# Antler.net
KiCad netlist of a schematic drawn in EAGLE
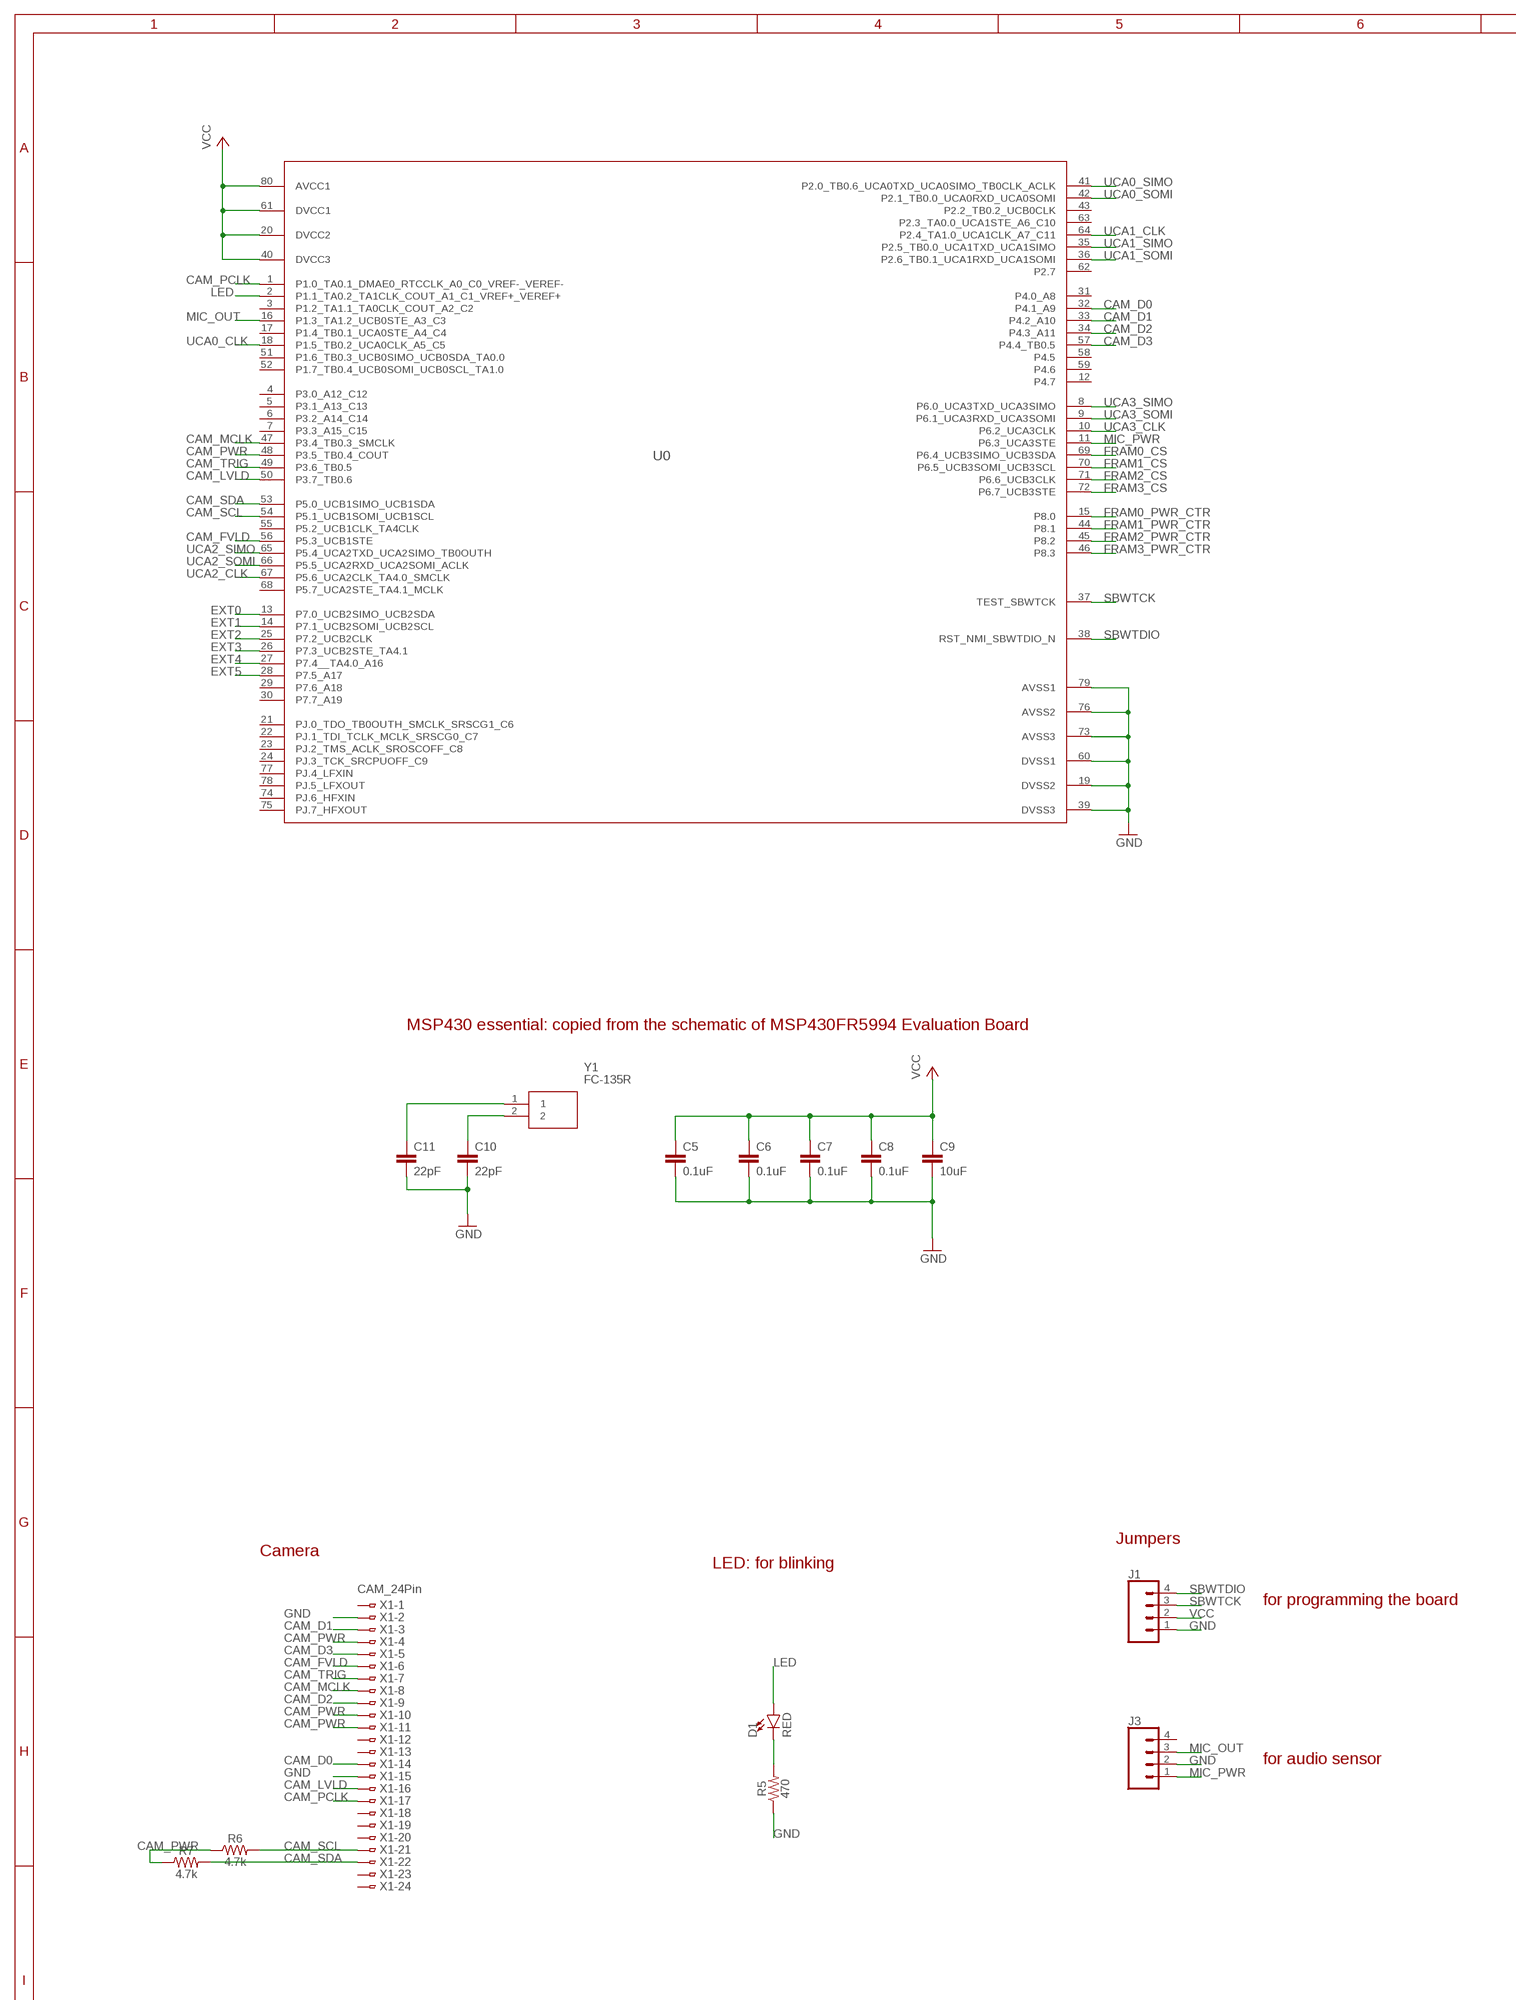
[diagram p0: schematic, sheet 1, part 1 of 2]
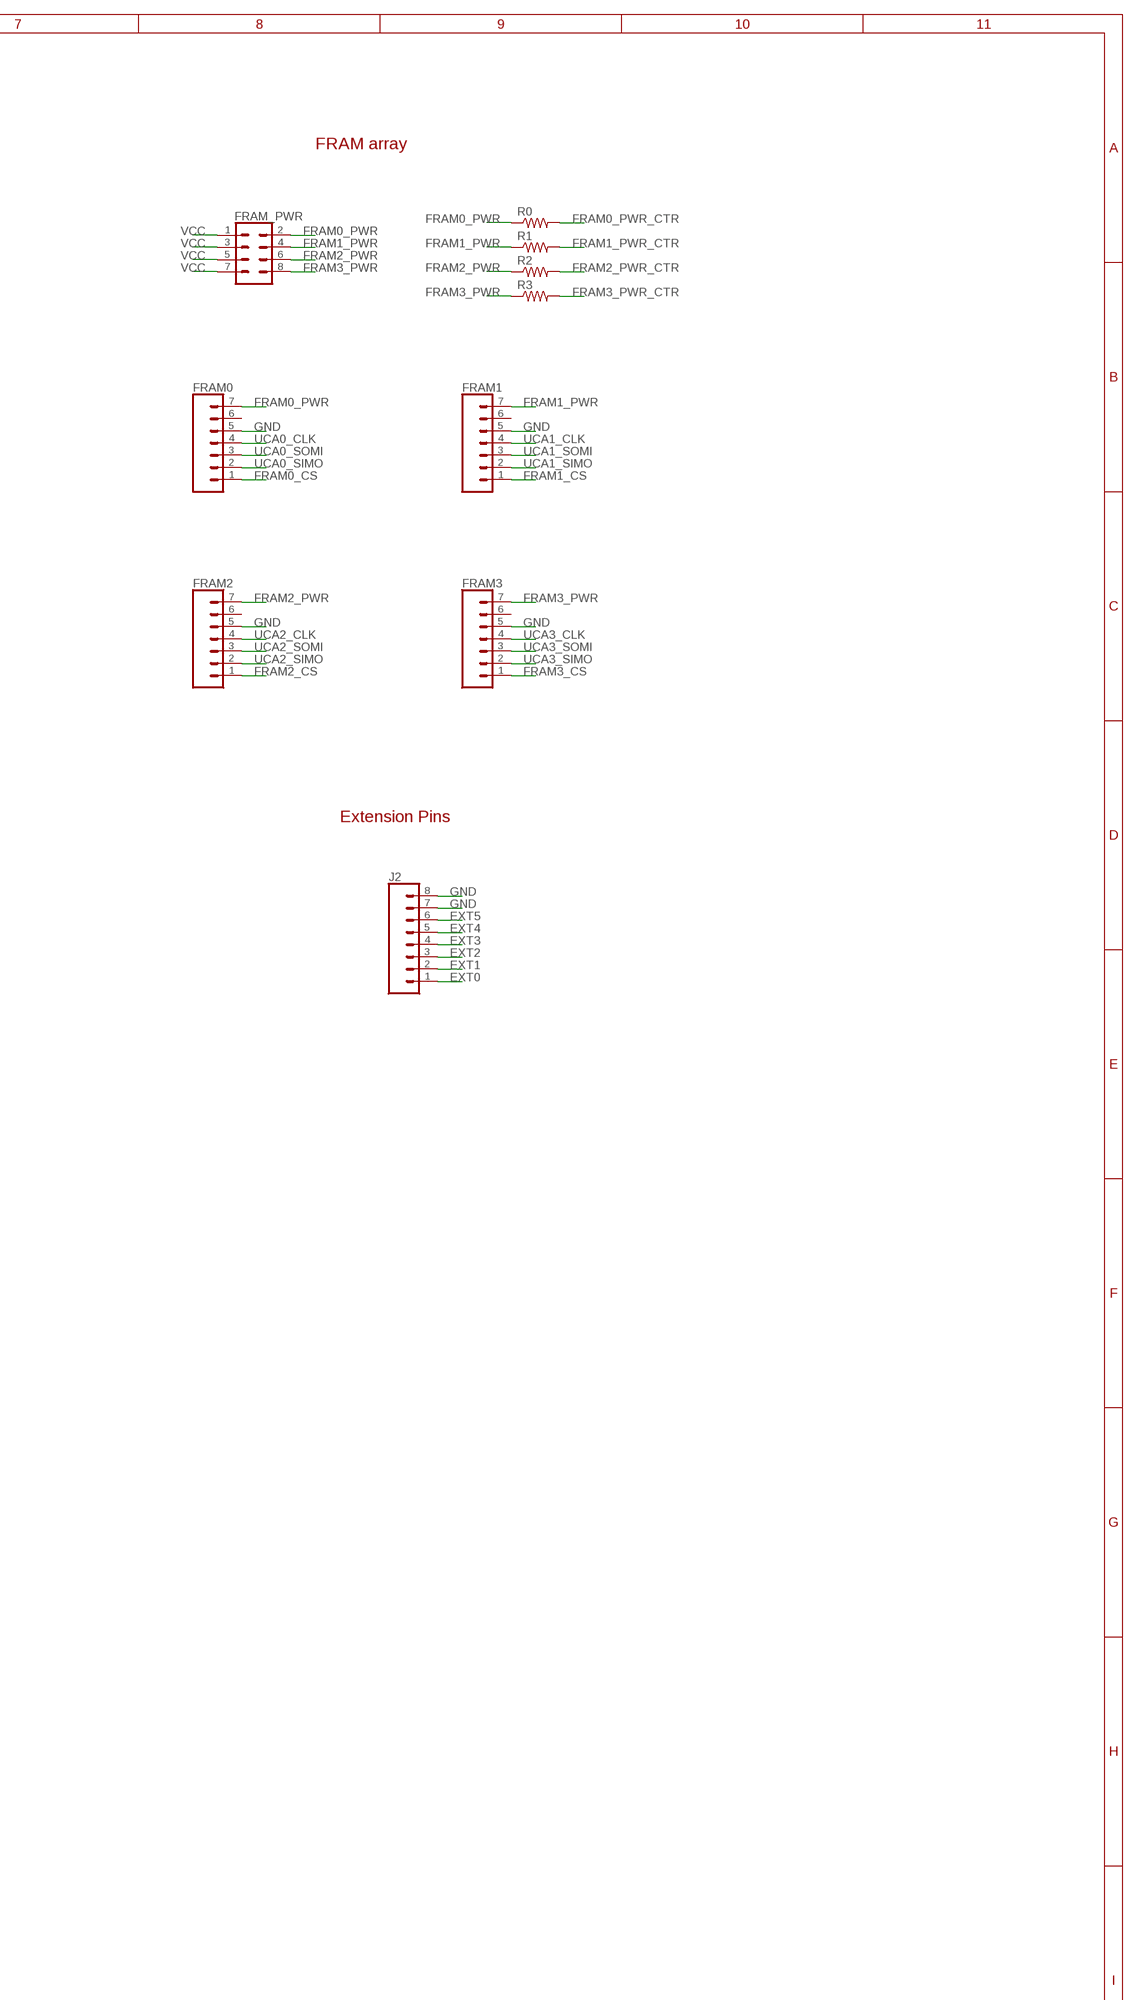
[diagram p1: schematic, sheet 1, part 2 of 2]

(export (version "E")
  (design (tool "Eeschema 10.0.6"))
  (components
    (comp (ref "C5")
      (value "0.1uF")
      (footprint "eagle-import:0603")
      (libsource (lib "eagle-import") (part "0.1UF-0603-25V-5%"))
    )
    (comp (ref "C6")
      (value "0.1uF")
      (footprint "eagle-import:0603")
      (libsource (lib "eagle-import") (part "0.1UF-0603-25V-5%"))
    )
    (comp (ref "C7")
      (value "0.1uF")
      (footprint "eagle-import:0603")
      (libsource (lib "eagle-import") (part "0.1UF-0603-25V-5%"))
    )
    (comp (ref "C8")
      (value "0.1uF")
      (footprint "eagle-import:0603")
      (libsource (lib "eagle-import") (part "0.1UF-0603-25V-5%"))
    )
    (comp (ref "C9")
      (value "10uF")
      (footprint "eagle-import:0603")
      (libsource (lib "eagle-import") (part "10UF-0603-6.3V-20%"))
    )
    (comp (ref "C10")
      (value "22pF")
      (footprint "eagle-import:0603")
      (libsource (lib "eagle-import") (part "22PF-0603-50V-5%"))
    )
    (comp (ref "C11")
      (value "22pF")
      (footprint "eagle-import:0603")
      (libsource (lib "eagle-import") (part "22PF-0603-50V-5%"))
    )
    (comp (ref "D1")
      (value "RED")
      (footprint "eagle-import:LED-0603")
      (libsource (lib "eagle-import") (part "LED-RED0603"))
    )
    (comp (ref "FRAM0")
      (value "CONN_07LOCK")
      (footprint "eagle-import:1X07_LOCK")
      (libsource (lib "eagle-import") (part "CONN_07LOCK"))
    )
    (comp (ref "FRAM1")
      (value "CONN_07LOCK")
      (footprint "eagle-import:1X07_LOCK")
      (libsource (lib "eagle-import") (part "CONN_07LOCK"))
    )
    (comp (ref "FRAM2")
      (value "CONN_07LOCK")
      (footprint "eagle-import:1X07_LOCK")
      (libsource (lib "eagle-import") (part "CONN_07LOCK"))
    )
    (comp (ref "FRAM3")
      (value "CONN_07LOCK")
      (footprint "eagle-import:1X07_LOCK")
      (libsource (lib "eagle-import") (part "CONN_07LOCK"))
    )
    (comp (ref "FRAM_PWR")
      (value "CONN_04X2")
      (footprint "eagle-import:2X4")
      (libsource (lib "eagle-import") (part "CONN_04X2"))
    )
    (comp (ref "J1")
      (value "CONN_04LOCK")
      (footprint "eagle-import:1X04_LOCK")
      (libsource (lib "eagle-import") (part "CONN_04LOCK"))
    )
    (comp (ref "J2")
      (value "CONN_08LOCK")
      (footprint "eagle-import:1X08_LOCK")
      (libsource (lib "eagle-import") (part "CONN_08LOCK"))
    )
    (comp (ref "J3")
      (value "CONN_04LOCK")
      (footprint "eagle-import:1X04_LOCK")
      (libsource (lib "eagle-import") (part "CONN_04LOCK"))
    )
    (comp (ref "R0")
      (value "R-US_R0603")
      (footprint "eagle-import:R0603")
      (libsource (lib "eagle-import") (part "R-US_R0603"))
    )
    (comp (ref "R1")
      (value "R-US_R0603")
      (footprint "eagle-import:R0603")
      (libsource (lib "eagle-import") (part "R-US_R0603"))
    )
    (comp (ref "R2")
      (value "R-US_R0603")
      (footprint "eagle-import:R0603")
      (libsource (lib "eagle-import") (part "R-US_R0603"))
    )
    (comp (ref "R3")
      (value "R-US_R0603")
      (footprint "eagle-import:R0603")
      (libsource (lib "eagle-import") (part "R-US_R0603"))
    )
    (comp (ref "R5")
      (value "470")
      (footprint "eagle-import:0603")
      (libsource (lib "eagle-import") (part "470OHM-0603-1/10W-1%"))
    )
    (comp (ref "R6")
      (value "4.7k")
      (footprint "eagle-import:0603")
      (libsource (lib "eagle-import") (part "4.7KOHM-0603-1/10W-1%"))
    )
    (comp (ref "R7")
      (value "4.7k")
      (footprint "eagle-import:0603")
      (libsource (lib "eagle-import") (part "4.7KOHM-0603-1/10W-1%"))
    )
    (comp (ref "U0")
      (value "MSP430FR5994PN")
      (footprint "eagle-import:PN0080A_N")
      (fields
        (field (name "MANUFACTURER") "Texas Instruments")
        (field (name "PARTNUMBER") "MSP430FR5994IPNR")
      )
      (libsource (lib "eagle-import") (part "MSP430FR5994IPN"))
    )
    (comp (ref "X1")
      (value "CAM_24Pin")
      (footprint "eagle-import:FH12-24S-0.5SH")
      (fields (field (name "MPN") "FH12-24S-0.5SH(55)"))
      (libsource (lib "eagle-import") (part "FH12-24S-0.5SH"))
    )
    (comp (ref "Y1")
      (value "FC-135R")
      (footprint "eagle-import:FC135327680KAAG0")
      (libsource (lib "eagle-import") (part "FC-135R"))
    )
  )
  (nets
    (net (code "1") (name "/CAM_D0") (class "Default")
      (node (ref "U0") (pin "32") (pinfunction "P4.1_A9_32") (pintype "bidirectional"))
      (node (ref "X1") (pin "14") (pinfunction "1_14") (pintype "passive"))
    )
    (net (code "2") (name "/CAM_D1") (class "Default")
      (node (ref "U0") (pin "33") (pinfunction "P4.2_A10_33") (pintype "bidirectional"))
      (node (ref "X1") (pin "3") (pinfunction "1_3") (pintype "passive"))
    )
    (net (code "3") (name "/CAM_D2") (class "Default")
      (node (ref "U0") (pin "34") (pinfunction "P4.3_A11_34") (pintype "bidirectional"))
      (node (ref "X1") (pin "9") (pinfunction "1_9") (pintype "passive"))
    )
    (net (code "4") (name "/CAM_D3") (class "Default")
      (node (ref "U0") (pin "57") (pinfunction "P4.4_TB0.5_57") (pintype "bidirectional"))
      (node (ref "X1") (pin "5") (pinfunction "1_5") (pintype "passive"))
    )
    (net (code "5") (name "/CAM_FVLD") (class "Default")
      (node (ref "U0") (pin "56") (pinfunction "P5.3_UCB1STE_56") (pintype "bidirectional"))
      (node (ref "X1") (pin "6") (pinfunction "1_6") (pintype "passive"))
    )
    (net (code "6") (name "/CAM_LVLD") (class "Default")
      (node (ref "U0") (pin "50") (pinfunction "P3.7_TB0.6_50") (pintype "bidirectional"))
      (node (ref "X1") (pin "16") (pinfunction "1_16") (pintype "passive"))
    )
    (net (code "7") (name "/CAM_MCLK") (class "Default")
      (node (ref "U0") (pin "47") (pinfunction "P3.4_TB0.3_SMCLK_47") (pintype "bidirectional"))
      (node (ref "X1") (pin "8") (pinfunction "1_8") (pintype "passive"))
    )
    (net (code "8") (name "/CAM_PCLK") (class "Default")
      (node (ref "U0") (pin "1") (pinfunction "P1.0_TA0.1_DMAE0_RTCCLK_A0_C0_VREF-_VEREF-_1") (pintype "bidirectional"))
      (node (ref "X1") (pin "17") (pinfunction "1_17") (pintype "passive"))
    )
    (net (code "9") (name "/CAM_PWR") (class "Default")
      (node (ref "R6") (pin "1") (pinfunction "1_1") (pintype "passive"))
      (node (ref "R7") (pin "1") (pinfunction "1_1") (pintype "passive"))
      (node (ref "U0") (pin "48") (pinfunction "P3.5_TB0.4_COUT_48") (pintype "bidirectional"))
      (node (ref "X1") (pin "10") (pinfunction "1_10") (pintype "passive"))
      (node (ref "X1") (pin "11") (pinfunction "1_11") (pintype "passive"))
      (node (ref "X1") (pin "4") (pinfunction "1_4") (pintype "passive"))
    )
    (net (code "10") (name "/CAM_SCL") (class "Default")
      (node (ref "R6") (pin "2") (pinfunction "2_2") (pintype "passive"))
      (node (ref "U0") (pin "54") (pinfunction "P5.1_UCB1SOMI_UCB1SCL_54") (pintype "bidirectional"))
      (node (ref "X1") (pin "21") (pinfunction "1_21") (pintype "passive"))
    )
    (net (code "11") (name "/CAM_SDA") (class "Default")
      (node (ref "R7") (pin "2") (pinfunction "2_2") (pintype "passive"))
      (node (ref "U0") (pin "53") (pinfunction "P5.0_UCB1SIMO_UCB1SDA_53") (pintype "bidirectional"))
      (node (ref "X1") (pin "22") (pinfunction "1_22") (pintype "passive"))
    )
    (net (code "12") (name "/CAM_TRIG") (class "Default")
      (node (ref "U0") (pin "49") (pinfunction "P3.6_TB0.5_49") (pintype "bidirectional"))
      (node (ref "X1") (pin "7") (pinfunction "1_7") (pintype "passive"))
    )
    (net (code "13") (name "/EXT0") (class "Default")
      (node (ref "J2") (pin "1") (pinfunction "1_1") (pintype "passive"))
      (node (ref "U0") (pin "13") (pinfunction "P7.0_UCB2SIMO_UCB2SDA_13") (pintype "bidirectional"))
    )
    (net (code "14") (name "/EXT1") (class "Default")
      (node (ref "J2") (pin "2") (pinfunction "2_2") (pintype "passive"))
      (node (ref "U0") (pin "14") (pinfunction "P7.1_UCB2SOMI_UCB2SCL_14") (pintype "bidirectional"))
    )
    (net (code "15") (name "/EXT2") (class "Default")
      (node (ref "J2") (pin "3") (pinfunction "3_3") (pintype "passive"))
      (node (ref "U0") (pin "25") (pinfunction "P7.2_UCB2CLK_25") (pintype "bidirectional"))
    )
    (net (code "16") (name "/EXT3") (class "Default")
      (node (ref "J2") (pin "4") (pinfunction "4_4") (pintype "passive"))
      (node (ref "U0") (pin "26") (pinfunction "P7.3_UCB2STE_TA4.1_26") (pintype "bidirectional"))
    )
    (net (code "17") (name "/EXT4") (class "Default")
      (node (ref "J2") (pin "5") (pinfunction "5_5") (pintype "passive"))
      (node (ref "U0") (pin "27") (pinfunction "P7.4__TA4.0_A16_27") (pintype "bidirectional"))
    )
    (net (code "18") (name "/EXT5") (class "Default")
      (node (ref "J2") (pin "6") (pinfunction "6_6") (pintype "passive"))
      (node (ref "U0") (pin "28") (pinfunction "P7.5_A17_28") (pintype "bidirectional"))
    )
    (net (code "19") (name "/FRAM0_CS") (class "Default")
      (node (ref "FRAM0") (pin "1") (pinfunction "1_1") (pintype "passive"))
      (node (ref "U0") (pin "69") (pinfunction "P6.4_UCB3SIMO_UCB3SDA_69") (pintype "bidirectional"))
    )
    (net (code "20") (name "/FRAM0_PWR") (class "Default")
      (node (ref "FRAM0") (pin "7") (pinfunction "7_7") (pintype "passive"))
      (node (ref "FRAM_PWR") (pin "2") (pinfunction "2_2") (pintype "passive"))
      (node (ref "R0") (pin "1") (pinfunction "1_1") (pintype "passive"))
    )
    (net (code "21") (name "/FRAM0_PWR_CTR") (class "Default")
      (node (ref "R0") (pin "2") (pinfunction "2_2") (pintype "passive"))
      (node (ref "U0") (pin "15") (pinfunction "P8.0_15") (pintype "bidirectional"))
    )
    (net (code "22") (name "/FRAM1_CS") (class "Default")
      (node (ref "FRAM1") (pin "1") (pinfunction "1_1") (pintype "passive"))
      (node (ref "U0") (pin "70") (pinfunction "P6.5_UCB3SOMI_UCB3SCL_70") (pintype "bidirectional"))
    )
    (net (code "23") (name "/FRAM1_PWR") (class "Default")
      (node (ref "FRAM1") (pin "7") (pinfunction "7_7") (pintype "passive"))
      (node (ref "FRAM_PWR") (pin "4") (pinfunction "4_4") (pintype "passive"))
      (node (ref "R1") (pin "1") (pinfunction "1_1") (pintype "passive"))
    )
    (net (code "24") (name "/FRAM1_PWR_CTR") (class "Default")
      (node (ref "R1") (pin "2") (pinfunction "2_2") (pintype "passive"))
      (node (ref "U0") (pin "44") (pinfunction "P8.1_44") (pintype "bidirectional"))
    )
    (net (code "25") (name "/FRAM2_CS") (class "Default")
      (node (ref "FRAM2") (pin "1") (pinfunction "1_1") (pintype "passive"))
      (node (ref "U0") (pin "71") (pinfunction "P6.6_UCB3CLK_71") (pintype "bidirectional"))
    )
    (net (code "26") (name "/FRAM2_PWR") (class "Default")
      (node (ref "FRAM2") (pin "7") (pinfunction "7_7") (pintype "passive"))
      (node (ref "FRAM_PWR") (pin "6") (pinfunction "6_6") (pintype "passive"))
      (node (ref "R2") (pin "1") (pinfunction "1_1") (pintype "passive"))
    )
    (net (code "27") (name "/FRAM2_PWR_CTR") (class "Default")
      (node (ref "R2") (pin "2") (pinfunction "2_2") (pintype "passive"))
      (node (ref "U0") (pin "45") (pinfunction "P8.2_45") (pintype "bidirectional"))
    )
    (net (code "28") (name "/FRAM3_CS") (class "Default")
      (node (ref "FRAM3") (pin "1") (pinfunction "1_1") (pintype "passive"))
      (node (ref "U0") (pin "72") (pinfunction "P6.7_UCB3STE_72") (pintype "bidirectional"))
    )
    (net (code "29") (name "/FRAM3_PWR") (class "Default")
      (node (ref "FRAM3") (pin "7") (pinfunction "7_7") (pintype "passive"))
      (node (ref "FRAM_PWR") (pin "8") (pinfunction "8_8") (pintype "passive"))
      (node (ref "R3") (pin "1") (pinfunction "1_1") (pintype "passive"))
    )
    (net (code "30") (name "/FRAM3_PWR_CTR") (class "Default")
      (node (ref "R3") (pin "2") (pinfunction "2_2") (pintype "passive"))
      (node (ref "U0") (pin "46") (pinfunction "P8.3_46") (pintype "bidirectional"))
    )
    (net (code "31") (name "/LED") (class "Default")
      (node (ref "D1") (pin "A") (pinfunction "A_A") (pintype "passive"))
      (node (ref "U0") (pin "2") (pinfunction "P1.1_TA0.2_TA1CLK_COUT_A1_C1_VREF+_VEREF+_2") (pintype "bidirectional"))
    )
    (net (code "32") (name "/MIC_OUT") (class "Default")
      (node (ref "J3") (pin "3") (pinfunction "3_3") (pintype "passive"))
      (node (ref "U0") (pin "16") (pinfunction "P1.3_TA1.2_UCB0STE_A3_C3_16") (pintype "bidirectional"))
    )
    (net (code "33") (name "/MIC_PWR") (class "Default")
      (node (ref "J3") (pin "1") (pinfunction "1_1") (pintype "passive"))
      (node (ref "U0") (pin "11") (pinfunction "P6.3_UCA3STE_11") (pintype "bidirectional"))
    )
    (net (code "34") (name "/SBWTCK") (class "Default")
      (node (ref "J1") (pin "3") (pinfunction "3_3") (pintype "passive"))
      (node (ref "U0") (pin "37") (pinfunction "TEST_SBWTCK_37") (pintype "input"))
    )
    (net (code "35") (name "/SBWTDIO") (class "Default")
      (node (ref "J1") (pin "4") (pinfunction "4_4") (pintype "passive"))
      (node (ref "U0") (pin "38") (pinfunction "RST_NMI_SBWTDIO_N_38") (pintype "bidirectional"))
    )
    (net (code "36") (name "/UCA0_CLK") (class "Default")
      (node (ref "FRAM0") (pin "4") (pinfunction "4_4") (pintype "passive"))
      (node (ref "U0") (pin "18") (pinfunction "P1.5_TB0.2_UCA0CLK_A5_C5_18") (pintype "bidirectional"))
    )
    (net (code "37") (name "/UCA0_SIMO") (class "Default")
      (node (ref "FRAM0") (pin "2") (pinfunction "2_2") (pintype "passive"))
      (node (ref "U0") (pin "41") (pinfunction "P2.0_TB0.6_UCA0TXD_UCA0SIMO_TB0CLK_ACLK_41") (pintype "bidirectional"))
    )
    (net (code "38") (name "/UCA0_SOMI") (class "Default")
      (node (ref "FRAM0") (pin "3") (pinfunction "3_3") (pintype "passive"))
      (node (ref "U0") (pin "42") (pinfunction "P2.1_TB0.0_UCA0RXD_UCA0SOMI_42") (pintype "bidirectional"))
    )
    (net (code "39") (name "/UCA1_CLK") (class "Default")
      (node (ref "FRAM1") (pin "4") (pinfunction "4_4") (pintype "passive"))
      (node (ref "U0") (pin "64") (pinfunction "P2.4_TA1.0_UCA1CLK_A7_C11_64") (pintype "bidirectional"))
    )
    (net (code "40") (name "/UCA1_SIMO") (class "Default")
      (node (ref "FRAM1") (pin "2") (pinfunction "2_2") (pintype "passive"))
      (node (ref "U0") (pin "35") (pinfunction "P2.5_TB0.0_UCA1TXD_UCA1SIMO_35") (pintype "bidirectional"))
    )
    (net (code "41") (name "/UCA1_SOMI") (class "Default")
      (node (ref "FRAM1") (pin "3") (pinfunction "3_3") (pintype "passive"))
      (node (ref "U0") (pin "36") (pinfunction "P2.6_TB0.1_UCA1RXD_UCA1SOMI_36") (pintype "bidirectional"))
    )
    (net (code "42") (name "/UCA2_CLK") (class "Default")
      (node (ref "FRAM2") (pin "4") (pinfunction "4_4") (pintype "passive"))
      (node (ref "U0") (pin "67") (pinfunction "P5.6_UCA2CLK_TA4.0_SMCLK_67") (pintype "bidirectional"))
    )
    (net (code "43") (name "/UCA2_SIMO") (class "Default")
      (node (ref "FRAM2") (pin "2") (pinfunction "2_2") (pintype "passive"))
      (node (ref "U0") (pin "65") (pinfunction "P5.4_UCA2TXD_UCA2SIMO_TB0OUTH_65") (pintype "bidirectional"))
    )
    (net (code "44") (name "/UCA2_SOMI") (class "Default")
      (node (ref "FRAM2") (pin "3") (pinfunction "3_3") (pintype "passive"))
      (node (ref "U0") (pin "66") (pinfunction "P5.5_UCA2RXD_UCA2SOMI_ACLK_66") (pintype "bidirectional"))
    )
    (net (code "45") (name "/UCA3_CLK") (class "Default")
      (node (ref "FRAM3") (pin "4") (pinfunction "4_4") (pintype "passive"))
      (node (ref "U0") (pin "10") (pinfunction "P6.2_UCA3CLK_10") (pintype "bidirectional"))
    )
    (net (code "46") (name "/UCA3_SIMO") (class "Default")
      (node (ref "FRAM3") (pin "2") (pinfunction "2_2") (pintype "passive"))
      (node (ref "U0") (pin "8") (pinfunction "P6.0_UCA3TXD_UCA3SIMO_8") (pintype "bidirectional"))
    )
    (net (code "47") (name "/UCA3_SOMI") (class "Default")
      (node (ref "FRAM3") (pin "3") (pinfunction "3_3") (pintype "passive"))
      (node (ref "U0") (pin "9") (pinfunction "P6.1_UCA3RXD_UCA3SOMI_9") (pintype "bidirectional"))
    )
    (net (code "48") (name "GND") (class "Default")
      (node (ref "C10") (pin "2") (pinfunction "2_2") (pintype "passive"))
      (node (ref "C11") (pin "2") (pinfunction "2_2") (pintype "passive"))
      (node (ref "C5") (pin "2") (pinfunction "2_2") (pintype "passive"))
      (node (ref "C6") (pin "2") (pinfunction "2_2") (pintype "passive"))
      (node (ref "C7") (pin "2") (pinfunction "2_2") (pintype "passive"))
      (node (ref "C8") (pin "2") (pinfunction "2_2") (pintype "passive"))
      (node (ref "C9") (pin "2") (pinfunction "2_2") (pintype "passive"))
      (node (ref "FRAM0") (pin "5") (pinfunction "5_5") (pintype "passive"))
      (node (ref "FRAM1") (pin "5") (pinfunction "5_5") (pintype "passive"))
      (node (ref "FRAM2") (pin "5") (pinfunction "5_5") (pintype "passive"))
      (node (ref "FRAM3") (pin "5") (pinfunction "5_5") (pintype "passive"))
      (node (ref "J1") (pin "1") (pinfunction "1_1") (pintype "passive"))
      (node (ref "J2") (pin "7") (pinfunction "7_7") (pintype "passive"))
      (node (ref "J2") (pin "8") (pinfunction "8_8") (pintype "passive"))
      (node (ref "J3") (pin "2") (pinfunction "2_2") (pintype "passive"))
      (node (ref "R5") (pin "1") (pinfunction "1_1") (pintype "passive"))
      (node (ref "U0") (pin "19") (pinfunction "DVSS2_19") (pintype "power_in"))
      (node (ref "U0") (pin "39") (pinfunction "DVSS3_39") (pintype "power_in"))
      (node (ref "U0") (pin "60") (pinfunction "DVSS1_60") (pintype "power_in"))
      (node (ref "U0") (pin "73") (pinfunction "AVSS3_73") (pintype "power_in"))
      (node (ref "U0") (pin "76") (pinfunction "AVSS2_76") (pintype "power_in"))
      (node (ref "U0") (pin "79") (pinfunction "AVSS1_79") (pintype "power_in"))
      (node (ref "X1") (pin "15") (pinfunction "1_15") (pintype "passive"))
      (node (ref "X1") (pin "2") (pinfunction "1_2") (pintype "passive"))
    )
    (net (code "49") (name "Net-(C10-Pad1)") (class "Default")
      (node (ref "C10") (pin "1") (pinfunction "1_1") (pintype "passive"))
      (node (ref "Y1") (pin "2") (pinfunction "2_2") (pintype "bidirectional"))
    )
    (net (code "50") (name "Net-(C11-Pad1)") (class "Default")
      (node (ref "C11") (pin "1") (pinfunction "1_1") (pintype "passive"))
      (node (ref "Y1") (pin "1") (pinfunction "1_1") (pintype "bidirectional"))
    )
    (net (code "51") (name "Net-(D1-PadC)") (class "Default")
      (node (ref "D1") (pin "C") (pinfunction "C_C") (pintype "passive"))
      (node (ref "R5") (pin "2") (pinfunction "2_2") (pintype "passive"))
    )
    (net (code "52") (name "VCC") (class "Default")
      (node (ref "C5") (pin "1") (pinfunction "1_1") (pintype "passive"))
      (node (ref "C6") (pin "1") (pinfunction "1_1") (pintype "passive"))
      (node (ref "C7") (pin "1") (pinfunction "1_1") (pintype "passive"))
      (node (ref "C8") (pin "1") (pinfunction "1_1") (pintype "passive"))
      (node (ref "C9") (pin "1") (pinfunction "1_1") (pintype "passive"))
      (node (ref "FRAM_PWR") (pin "1") (pinfunction "1_1") (pintype "passive"))
      (node (ref "FRAM_PWR") (pin "3") (pinfunction "3_3") (pintype "passive"))
      (node (ref "FRAM_PWR") (pin "5") (pinfunction "5_5") (pintype "passive"))
      (node (ref "FRAM_PWR") (pin "7") (pinfunction "7_7") (pintype "passive"))
      (node (ref "J1") (pin "2") (pinfunction "2_2") (pintype "passive"))
      (node (ref "U0") (pin "20") (pinfunction "DVCC2_20") (pintype "power_in"))
      (node (ref "U0") (pin "40") (pinfunction "DVCC3_40") (pintype "power_in"))
      (node (ref "U0") (pin "61") (pinfunction "DVCC1_61") (pintype "power_in"))
      (node (ref "U0") (pin "80") (pinfunction "AVCC1_80") (pintype "power_in"))
    )
    (net (code "53") (name "unconnected-(FRAM0-Pad6)") (class "Default")
      (node (ref "FRAM0") (pin "6") (pinfunction "6_6") (pintype "passive"))
    )
    (net (code "54") (name "unconnected-(FRAM1-Pad6)") (class "Default")
      (node (ref "FRAM1") (pin "6") (pinfunction "6_6") (pintype "passive"))
    )
    (net (code "55") (name "unconnected-(FRAM2-Pad6)") (class "Default")
      (node (ref "FRAM2") (pin "6") (pinfunction "6_6") (pintype "passive"))
    )
    (net (code "56") (name "unconnected-(FRAM3-Pad6)") (class "Default")
      (node (ref "FRAM3") (pin "6") (pinfunction "6_6") (pintype "passive"))
    )
    (net (code "57") (name "unconnected-(J3-Pad4)") (class "Default")
      (node (ref "J3") (pin "4") (pinfunction "4_4") (pintype "passive"))
    )
    (net (code "58") (name "unconnected-(U0-P1.2_TA1.1_TA0CLK_COUT_A2_C2-Pad3)") (class "Default")
      (node (ref "U0") (pin "3") (pinfunction "P1.2_TA1.1_TA0CLK_COUT_A2_C2_3") (pintype "bidirectional"))
    )
    (net (code "59") (name "unconnected-(U0-P1.4_TB0.1_UCA0STE_A4_C4-Pad17)") (class "Default")
      (node (ref "U0") (pin "17") (pinfunction "P1.4_TB0.1_UCA0STE_A4_C4_17") (pintype "bidirectional"))
    )
    (net (code "60") (name "unconnected-(U0-P1.6_TB0.3_UCB0SIMO_UCB0SDA_TA0.0-Pad51)") (class "Default")
      (node (ref "U0") (pin "51") (pinfunction "P1.6_TB0.3_UCB0SIMO_UCB0SDA_TA0.0_51") (pintype "bidirectional"))
    )
    (net (code "61") (name "unconnected-(U0-P1.7_TB0.4_UCB0SOMI_UCB0SCL_TA1.0-Pad52)") (class "Default")
      (node (ref "U0") (pin "52") (pinfunction "P1.7_TB0.4_UCB0SOMI_UCB0SCL_TA1.0_52") (pintype "bidirectional"))
    )
    (net (code "62") (name "unconnected-(U0-P2.2_TB0.2_UCB0CLK-Pad43)") (class "Default")
      (node (ref "U0") (pin "43") (pinfunction "P2.2_TB0.2_UCB0CLK_43") (pintype "bidirectional"))
    )
    (net (code "63") (name "unconnected-(U0-P2.3_TA0.0_UCA1STE_A6_C10-Pad63)") (class "Default")
      (node (ref "U0") (pin "63") (pinfunction "P2.3_TA0.0_UCA1STE_A6_C10_63") (pintype "bidirectional"))
    )
    (net (code "64") (name "unconnected-(U0-P2.7-Pad62)") (class "Default")
      (node (ref "U0") (pin "62") (pinfunction "P2.7_62") (pintype "bidirectional"))
    )
    (net (code "65") (name "unconnected-(U0-P3.0_A12_C12-Pad4)") (class "Default")
      (node (ref "U0") (pin "4") (pinfunction "P3.0_A12_C12_4") (pintype "bidirectional"))
    )
    (net (code "66") (name "unconnected-(U0-P3.1_A13_C13-Pad5)") (class "Default")
      (node (ref "U0") (pin "5") (pinfunction "P3.1_A13_C13_5") (pintype "bidirectional"))
    )
    (net (code "67") (name "unconnected-(U0-P3.2_A14_C14-Pad6)") (class "Default")
      (node (ref "U0") (pin "6") (pinfunction "P3.2_A14_C14_6") (pintype "bidirectional"))
    )
    (net (code "68") (name "unconnected-(U0-P3.3_A15_C15-Pad7)") (class "Default")
      (node (ref "U0") (pin "7") (pinfunction "P3.3_A15_C15_7") (pintype "bidirectional"))
    )
    (net (code "69") (name "unconnected-(U0-P4.0_A8-Pad31)") (class "Default")
      (node (ref "U0") (pin "31") (pinfunction "P4.0_A8_31") (pintype "bidirectional"))
    )
    (net (code "70") (name "unconnected-(U0-P4.5-Pad58)") (class "Default")
      (node (ref "U0") (pin "58") (pinfunction "P4.5_58") (pintype "bidirectional"))
    )
    (net (code "71") (name "unconnected-(U0-P4.6-Pad59)") (class "Default")
      (node (ref "U0") (pin "59") (pinfunction "P4.6_59") (pintype "bidirectional"))
    )
    (net (code "72") (name "unconnected-(U0-P4.7-Pad12)") (class "Default")
      (node (ref "U0") (pin "12") (pinfunction "P4.7_12") (pintype "bidirectional"))
    )
    (net (code "73") (name "unconnected-(U0-P5.2_UCB1CLK_TA4CLK-Pad55)") (class "Default")
      (node (ref "U0") (pin "55") (pinfunction "P5.2_UCB1CLK_TA4CLK_55") (pintype "bidirectional"))
    )
    (net (code "74") (name "unconnected-(U0-P5.7_UCA2STE_TA4.1_MCLK-Pad68)") (class "Default")
      (node (ref "U0") (pin "68") (pinfunction "P5.7_UCA2STE_TA4.1_MCLK_68") (pintype "bidirectional"))
    )
    (net (code "75") (name "unconnected-(U0-P7.6_A18-Pad29)") (class "Default")
      (node (ref "U0") (pin "29") (pinfunction "P7.6_A18_29") (pintype "bidirectional"))
    )
    (net (code "76") (name "unconnected-(U0-P7.7_A19-Pad30)") (class "Default")
      (node (ref "U0") (pin "30") (pinfunction "P7.7_A19_30") (pintype "bidirectional"))
    )
    (net (code "77") (name "unconnected-(U0-PJ.0_TDO_TB0OUTH_SMCLK_SRSCG1_C6-Pad21)") (class "Default")
      (node (ref "U0") (pin "21") (pinfunction "PJ.0_TDO_TB0OUTH_SMCLK_SRSCG1_C6_21") (pintype "bidirectional"))
    )
    (net (code "78") (name "unconnected-(U0-PJ.1_TDI_TCLK_MCLK_SRSCG0_C7-Pad22)") (class "Default")
      (node (ref "U0") (pin "22") (pinfunction "PJ.1_TDI_TCLK_MCLK_SRSCG0_C7_22") (pintype "bidirectional"))
    )
    (net (code "79") (name "unconnected-(U0-PJ.2_TMS_ACLK_SROSCOFF_C8-Pad23)") (class "Default")
      (node (ref "U0") (pin "23") (pinfunction "PJ.2_TMS_ACLK_SROSCOFF_C8_23") (pintype "bidirectional"))
    )
    (net (code "80") (name "unconnected-(U0-PJ.3_TCK_SRCPUOFF_C9-Pad24)") (class "Default")
      (node (ref "U0") (pin "24") (pinfunction "PJ.3_TCK_SRCPUOFF_C9_24") (pintype "bidirectional"))
    )
    (net (code "81") (name "unconnected-(U0-PJ.4_LFXIN-Pad77)") (class "Default")
      (node (ref "U0") (pin "77") (pinfunction "PJ.4_LFXIN_77") (pintype "bidirectional"))
    )
    (net (code "82") (name "unconnected-(U0-PJ.5_LFXOUT-Pad78)") (class "Default")
      (node (ref "U0") (pin "78") (pinfunction "PJ.5_LFXOUT_78") (pintype "bidirectional"))
    )
    (net (code "83") (name "unconnected-(U0-PJ.6_HFXIN-Pad74)") (class "Default")
      (node (ref "U0") (pin "74") (pinfunction "PJ.6_HFXIN_74") (pintype "bidirectional"))
    )
    (net (code "84") (name "unconnected-(U0-PJ.7_HFXOUT-Pad75)") (class "Default")
      (node (ref "U0") (pin "75") (pinfunction "PJ.7_HFXOUT_75") (pintype "bidirectional"))
    )
    (net (code "85") (name "unconnected-(X1-Pad1)") (class "Default")
      (node (ref "X1") (pin "1") (pinfunction "1_1") (pintype "passive"))
    )
    (net (code "86") (name "unconnected-(X1D-1-Pad12)") (class "Default")
      (node (ref "X1") (pin "12") (pinfunction "1_12") (pintype "passive"))
    )
    (net (code "87") (name "unconnected-(X1E-1-Pad13)") (class "Default")
      (node (ref "X1") (pin "13") (pinfunction "1_13") (pintype "passive"))
    )
    (net (code "88") (name "unconnected-(X1J-1-Pad18)") (class "Default")
      (node (ref "X1") (pin "18") (pinfunction "1_18") (pintype "passive"))
    )
    (net (code "89") (name "unconnected-(X1K-1-Pad19)") (class "Default")
      (node (ref "X1") (pin "19") (pinfunction "1_19") (pintype "passive"))
    )
    (net (code "90") (name "unconnected-(X1M-1-Pad20)") (class "Default")
      (node (ref "X1") (pin "20") (pinfunction "1_20") (pintype "passive"))
    )
    (net (code "91") (name "unconnected-(X1P-1-Pad23)") (class "Default")
      (node (ref "X1") (pin "23") (pinfunction "1_23") (pintype "passive"))
    )
    (net (code "92") (name "unconnected-(X1Q-1-Pad24)") (class "Default")
      (node (ref "X1") (pin "24") (pinfunction "1_24") (pintype "passive"))
    )
  )
)
